# 8x8_328.net
KiCad netlist of a schematic drawn in EAGLE
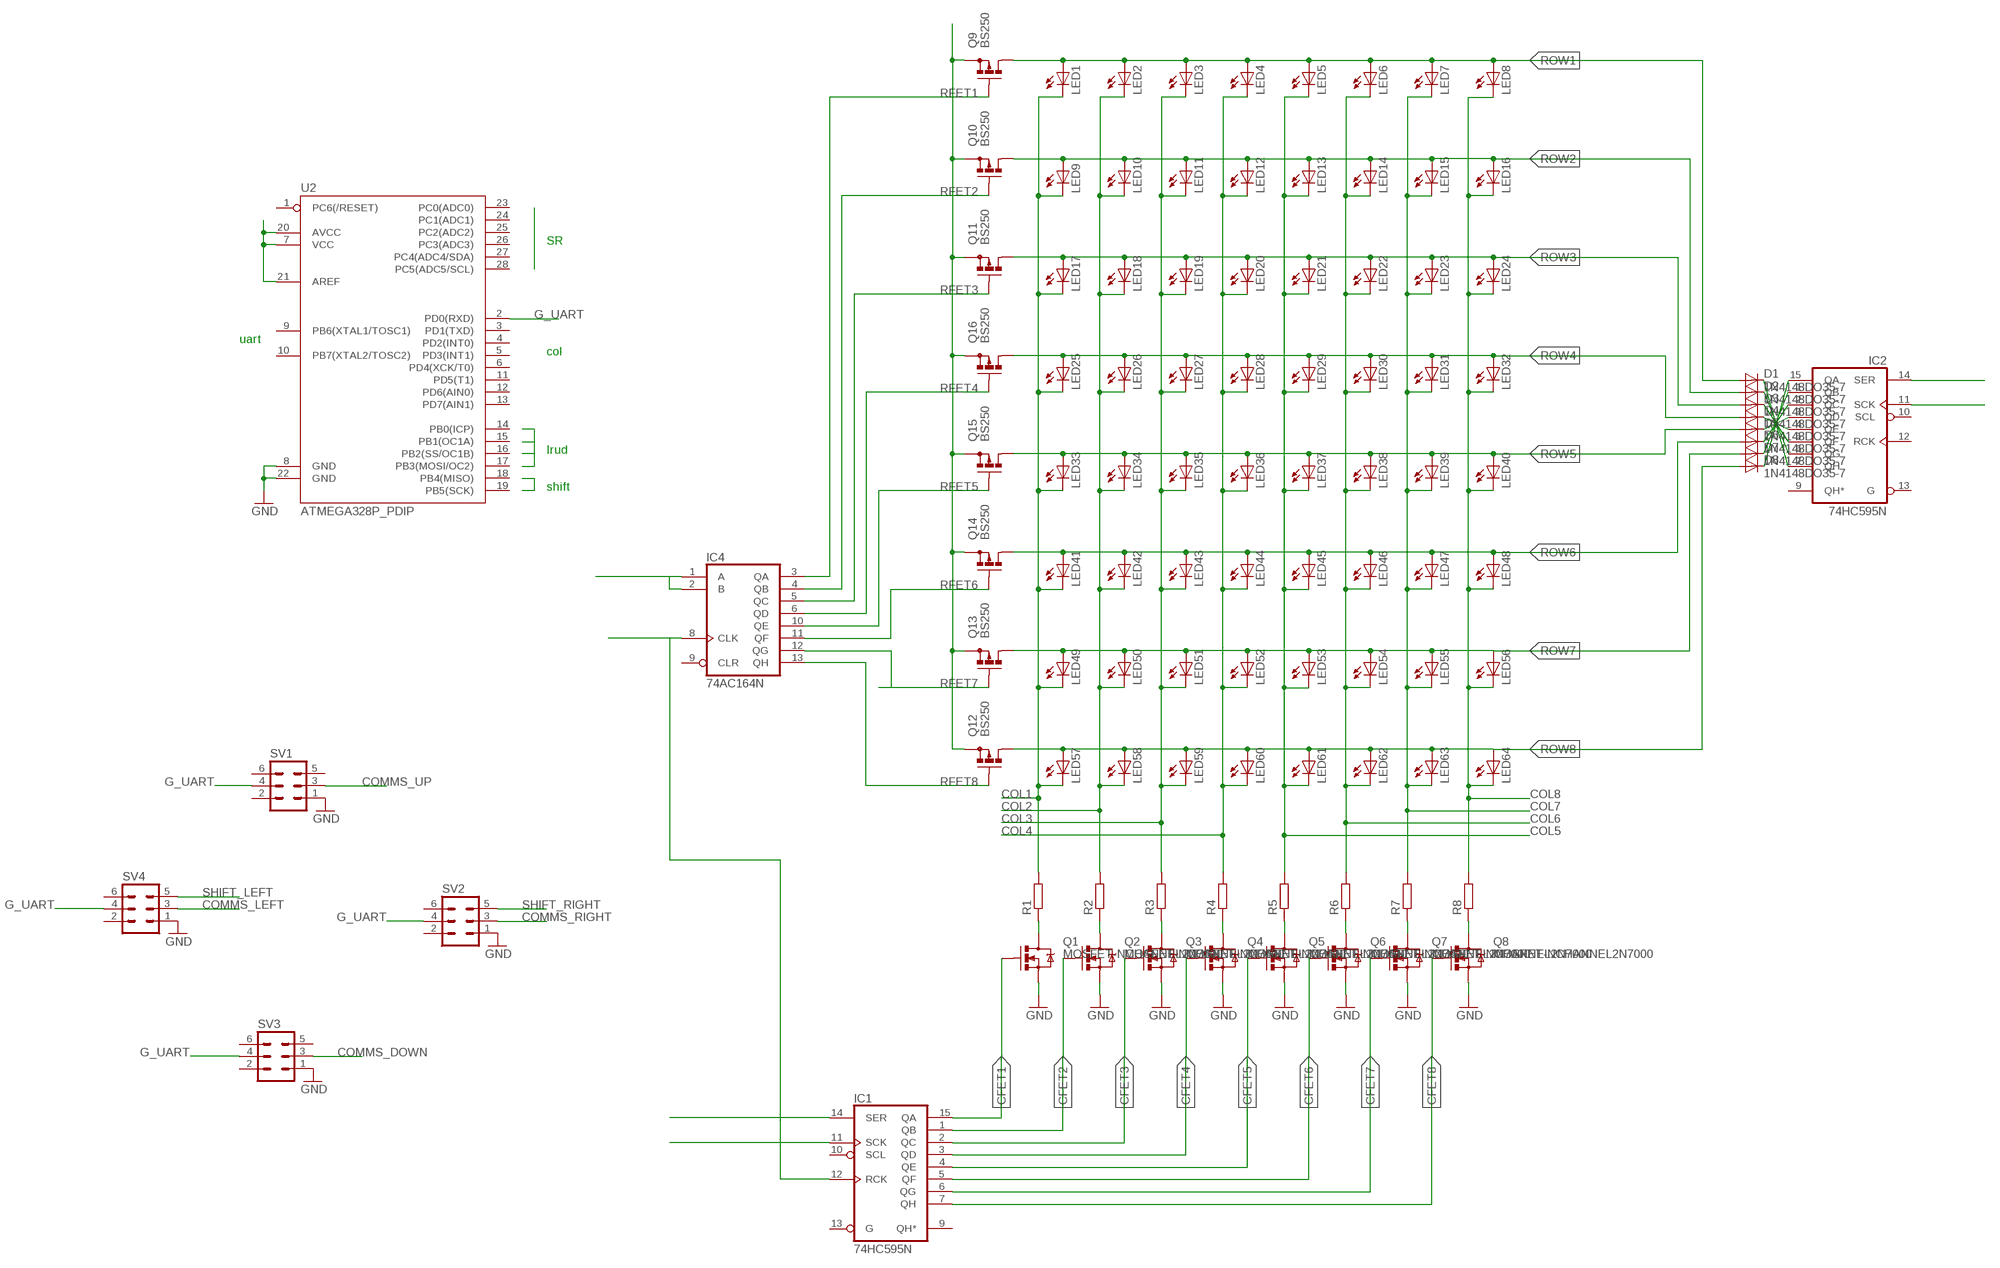
[diagram p0: schematic, sheet 1]

(export (version "E")
  (design (tool "Eeschema 10.0.6"))
  (components
    (comp (ref "D1")
      (value "1N4148DO35-7")
      (footprint "eagle-import:DO35-7")
      (libsource (lib "eagle-import") (part "1N4148DO35-7"))
    )
    (comp (ref "D2")
      (value "1N4148DO35-7")
      (footprint "eagle-import:DO35-7")
      (libsource (lib "eagle-import") (part "1N4148DO35-7"))
    )
    (comp (ref "D3")
      (value "1N4148DO35-7")
      (footprint "eagle-import:DO35-7")
      (libsource (lib "eagle-import") (part "1N4148DO35-7"))
    )
    (comp (ref "D4")
      (value "1N4148DO35-7")
      (footprint "eagle-import:DO35-7")
      (libsource (lib "eagle-import") (part "1N4148DO35-7"))
    )
    (comp (ref "D5")
      (value "1N4148DO35-7")
      (footprint "eagle-import:DO35-7")
      (libsource (lib "eagle-import") (part "1N4148DO35-7"))
    )
    (comp (ref "D6")
      (value "1N4148DO35-7")
      (footprint "eagle-import:DO35-7")
      (libsource (lib "eagle-import") (part "1N4148DO35-7"))
    )
    (comp (ref "D7")
      (value "1N4148DO35-7")
      (footprint "eagle-import:DO35-7")
      (libsource (lib "eagle-import") (part "1N4148DO35-7"))
    )
    (comp (ref "D8")
      (value "1N4148DO35-7")
      (footprint "eagle-import:DO35-7")
      (libsource (lib "eagle-import") (part "1N4148DO35-7"))
    )
    (comp (ref "IC1")
      (value "74HC595N")
      (footprint "eagle-import:DIL16")
      (libsource (lib "eagle-import") (part "74595NHC"))
    )
    (comp (ref "IC2")
      (value "74HC595N")
      (footprint "eagle-import:DIL16")
      (libsource (lib "eagle-import") (part "74595NHC"))
    )
    (comp (ref "IC4")
      (value "74AC164N")
      (footprint "eagle-import:DIL14")
      (libsource (lib "eagle-import") (part "74164NAC"))
    )
    (comp (ref "LED1")
      (value "LED5MM")
      (footprint "eagle-import:LED5MM")
      (libsource (lib "eagle-import") (part "LED5MM"))
    )
    (comp (ref "LED2")
      (value "LED5MM")
      (footprint "eagle-import:LED5MM")
      (libsource (lib "eagle-import") (part "LED5MM"))
    )
    (comp (ref "LED3")
      (value "LED5MM")
      (footprint "eagle-import:LED5MM")
      (libsource (lib "eagle-import") (part "LED5MM"))
    )
    (comp (ref "LED4")
      (value "LED5MM")
      (footprint "eagle-import:LED5MM")
      (libsource (lib "eagle-import") (part "LED5MM"))
    )
    (comp (ref "LED5")
      (value "LED5MM")
      (footprint "eagle-import:LED5MM")
      (libsource (lib "eagle-import") (part "LED5MM"))
    )
    (comp (ref "LED6")
      (value "LED5MM")
      (footprint "eagle-import:LED5MM")
      (libsource (lib "eagle-import") (part "LED5MM"))
    )
    (comp (ref "LED7")
      (value "LED5MM")
      (footprint "eagle-import:LED5MM")
      (libsource (lib "eagle-import") (part "LED5MM"))
    )
    (comp (ref "LED8")
      (value "LED5MM")
      (footprint "eagle-import:LED5MM")
      (libsource (lib "eagle-import") (part "LED5MM"))
    )
    (comp (ref "LED9")
      (value "LED5MM")
      (footprint "eagle-import:LED5MM")
      (libsource (lib "eagle-import") (part "LED5MM"))
    )
    (comp (ref "LED10")
      (value "LED5MM")
      (footprint "eagle-import:LED5MM")
      (libsource (lib "eagle-import") (part "LED5MM"))
    )
    (comp (ref "LED11")
      (value "LED5MM")
      (footprint "eagle-import:LED5MM")
      (libsource (lib "eagle-import") (part "LED5MM"))
    )
    (comp (ref "LED12")
      (value "LED5MM")
      (footprint "eagle-import:LED5MM")
      (libsource (lib "eagle-import") (part "LED5MM"))
    )
    (comp (ref "LED13")
      (value "LED5MM")
      (footprint "eagle-import:LED5MM")
      (libsource (lib "eagle-import") (part "LED5MM"))
    )
    (comp (ref "LED14")
      (value "LED5MM")
      (footprint "eagle-import:LED5MM")
      (libsource (lib "eagle-import") (part "LED5MM"))
    )
    (comp (ref "LED15")
      (value "LED5MM")
      (footprint "eagle-import:LED5MM")
      (libsource (lib "eagle-import") (part "LED5MM"))
    )
    (comp (ref "LED16")
      (value "LED5MM")
      (footprint "eagle-import:LED5MM")
      (libsource (lib "eagle-import") (part "LED5MM"))
    )
    (comp (ref "LED17")
      (value "LED5MM")
      (footprint "eagle-import:LED5MM")
      (libsource (lib "eagle-import") (part "LED5MM"))
    )
    (comp (ref "LED18")
      (value "LED5MM")
      (footprint "eagle-import:LED5MM")
      (libsource (lib "eagle-import") (part "LED5MM"))
    )
    (comp (ref "LED19")
      (value "LED5MM")
      (footprint "eagle-import:LED5MM")
      (libsource (lib "eagle-import") (part "LED5MM"))
    )
    (comp (ref "LED20")
      (value "LED5MM")
      (footprint "eagle-import:LED5MM")
      (libsource (lib "eagle-import") (part "LED5MM"))
    )
    (comp (ref "LED21")
      (value "LED5MM")
      (footprint "eagle-import:LED5MM")
      (libsource (lib "eagle-import") (part "LED5MM"))
    )
    (comp (ref "LED22")
      (value "LED5MM")
      (footprint "eagle-import:LED5MM")
      (libsource (lib "eagle-import") (part "LED5MM"))
    )
    (comp (ref "LED23")
      (value "LED5MM")
      (footprint "eagle-import:LED5MM")
      (libsource (lib "eagle-import") (part "LED5MM"))
    )
    (comp (ref "LED24")
      (value "LED5MM")
      (footprint "eagle-import:LED5MM")
      (libsource (lib "eagle-import") (part "LED5MM"))
    )
    (comp (ref "LED25")
      (value "LED5MM")
      (footprint "eagle-import:LED5MM")
      (libsource (lib "eagle-import") (part "LED5MM"))
    )
    (comp (ref "LED26")
      (value "LED5MM")
      (footprint "eagle-import:LED5MM")
      (libsource (lib "eagle-import") (part "LED5MM"))
    )
    (comp (ref "LED27")
      (value "LED5MM")
      (footprint "eagle-import:LED5MM")
      (libsource (lib "eagle-import") (part "LED5MM"))
    )
    (comp (ref "LED28")
      (value "LED5MM")
      (footprint "eagle-import:LED5MM")
      (libsource (lib "eagle-import") (part "LED5MM"))
    )
    (comp (ref "LED29")
      (value "LED5MM")
      (footprint "eagle-import:LED5MM")
      (libsource (lib "eagle-import") (part "LED5MM"))
    )
    (comp (ref "LED30")
      (value "LED5MM")
      (footprint "eagle-import:LED5MM")
      (libsource (lib "eagle-import") (part "LED5MM"))
    )
    (comp (ref "LED31")
      (value "LED5MM")
      (footprint "eagle-import:LED5MM")
      (libsource (lib "eagle-import") (part "LED5MM"))
    )
    (comp (ref "LED32")
      (value "LED5MM")
      (footprint "eagle-import:LED5MM")
      (libsource (lib "eagle-import") (part "LED5MM"))
    )
    (comp (ref "LED33")
      (value "LED5MM")
      (footprint "eagle-import:LED5MM")
      (libsource (lib "eagle-import") (part "LED5MM"))
    )
    (comp (ref "LED34")
      (value "LED5MM")
      (footprint "eagle-import:LED5MM")
      (libsource (lib "eagle-import") (part "LED5MM"))
    )
    (comp (ref "LED35")
      (value "LED5MM")
      (footprint "eagle-import:LED5MM")
      (libsource (lib "eagle-import") (part "LED5MM"))
    )
    (comp (ref "LED36")
      (value "LED5MM")
      (footprint "eagle-import:LED5MM")
      (libsource (lib "eagle-import") (part "LED5MM"))
    )
    (comp (ref "LED37")
      (value "LED5MM")
      (footprint "eagle-import:LED5MM")
      (libsource (lib "eagle-import") (part "LED5MM"))
    )
    (comp (ref "LED38")
      (value "LED5MM")
      (footprint "eagle-import:LED5MM")
      (libsource (lib "eagle-import") (part "LED5MM"))
    )
    (comp (ref "LED39")
      (value "LED5MM")
      (footprint "eagle-import:LED5MM")
      (libsource (lib "eagle-import") (part "LED5MM"))
    )
    (comp (ref "LED40")
      (value "LED5MM")
      (footprint "eagle-import:LED5MM")
      (libsource (lib "eagle-import") (part "LED5MM"))
    )
    (comp (ref "LED41")
      (value "LED5MM")
      (footprint "eagle-import:LED5MM")
      (libsource (lib "eagle-import") (part "LED5MM"))
    )
    (comp (ref "LED42")
      (value "LED5MM")
      (footprint "eagle-import:LED5MM")
      (libsource (lib "eagle-import") (part "LED5MM"))
    )
    (comp (ref "LED43")
      (value "LED5MM")
      (footprint "eagle-import:LED5MM")
      (libsource (lib "eagle-import") (part "LED5MM"))
    )
    (comp (ref "LED44")
      (value "LED5MM")
      (footprint "eagle-import:LED5MM")
      (libsource (lib "eagle-import") (part "LED5MM"))
    )
    (comp (ref "LED45")
      (value "LED5MM")
      (footprint "eagle-import:LED5MM")
      (libsource (lib "eagle-import") (part "LED5MM"))
    )
    (comp (ref "LED46")
      (value "LED5MM")
      (footprint "eagle-import:LED5MM")
      (libsource (lib "eagle-import") (part "LED5MM"))
    )
    (comp (ref "LED47")
      (value "LED5MM")
      (footprint "eagle-import:LED5MM")
      (libsource (lib "eagle-import") (part "LED5MM"))
    )
    (comp (ref "LED48")
      (value "LED5MM")
      (footprint "eagle-import:LED5MM")
      (libsource (lib "eagle-import") (part "LED5MM"))
    )
    (comp (ref "LED49")
      (value "LED5MM")
      (footprint "eagle-import:LED5MM")
      (libsource (lib "eagle-import") (part "LED5MM"))
    )
    (comp (ref "LED50")
      (value "LED5MM")
      (footprint "eagle-import:LED5MM")
      (libsource (lib "eagle-import") (part "LED5MM"))
    )
    (comp (ref "LED51")
      (value "LED5MM")
      (footprint "eagle-import:LED5MM")
      (libsource (lib "eagle-import") (part "LED5MM"))
    )
    (comp (ref "LED52")
      (value "LED5MM")
      (footprint "eagle-import:LED5MM")
      (libsource (lib "eagle-import") (part "LED5MM"))
    )
    (comp (ref "LED53")
      (value "LED5MM")
      (footprint "eagle-import:LED5MM")
      (libsource (lib "eagle-import") (part "LED5MM"))
    )
    (comp (ref "LED54")
      (value "LED5MM")
      (footprint "eagle-import:LED5MM")
      (libsource (lib "eagle-import") (part "LED5MM"))
    )
    (comp (ref "LED55")
      (value "LED5MM")
      (footprint "eagle-import:LED5MM")
      (libsource (lib "eagle-import") (part "LED5MM"))
    )
    (comp (ref "LED56")
      (value "LED5MM")
      (footprint "eagle-import:LED5MM")
      (libsource (lib "eagle-import") (part "LED5MM"))
    )
    (comp (ref "LED57")
      (value "LED5MM")
      (footprint "eagle-import:LED5MM")
      (libsource (lib "eagle-import") (part "LED5MM"))
    )
    (comp (ref "LED58")
      (value "LED5MM")
      (footprint "eagle-import:LED5MM")
      (libsource (lib "eagle-import") (part "LED5MM"))
    )
    (comp (ref "LED59")
      (value "LED5MM")
      (footprint "eagle-import:LED5MM")
      (libsource (lib "eagle-import") (part "LED5MM"))
    )
    (comp (ref "LED60")
      (value "LED5MM")
      (footprint "eagle-import:LED5MM")
      (libsource (lib "eagle-import") (part "LED5MM"))
    )
    (comp (ref "LED61")
      (value "LED5MM")
      (footprint "eagle-import:LED5MM")
      (libsource (lib "eagle-import") (part "LED5MM"))
    )
    (comp (ref "LED62")
      (value "LED5MM")
      (footprint "eagle-import:LED5MM")
      (libsource (lib "eagle-import") (part "LED5MM"))
    )
    (comp (ref "LED63")
      (value "LED5MM")
      (footprint "eagle-import:LED5MM")
      (libsource (lib "eagle-import") (part "LED5MM"))
    )
    (comp (ref "LED64")
      (value "LED5MM")
      (footprint "eagle-import:LED5MM")
      (libsource (lib "eagle-import") (part "LED5MM"))
    )
    (comp (ref "Q1")
      (value "MOSFET-NCHANNEL2N7000")
      (footprint "eagle-import:TO-92")
      (libsource (lib "eagle-import") (part "MOSFET-NCHANNEL2N7000"))
    )
    (comp (ref "Q2")
      (value "MOSFET-NCHANNEL2N7000")
      (footprint "eagle-import:TO-92")
      (libsource (lib "eagle-import") (part "MOSFET-NCHANNEL2N7000"))
    )
    (comp (ref "Q3")
      (value "MOSFET-NCHANNEL2N7000")
      (footprint "eagle-import:TO-92")
      (libsource (lib "eagle-import") (part "MOSFET-NCHANNEL2N7000"))
    )
    (comp (ref "Q4")
      (value "MOSFET-NCHANNEL2N7000")
      (footprint "eagle-import:TO-92")
      (libsource (lib "eagle-import") (part "MOSFET-NCHANNEL2N7000"))
    )
    (comp (ref "Q5")
      (value "MOSFET-NCHANNEL2N7000")
      (footprint "eagle-import:TO-92")
      (libsource (lib "eagle-import") (part "MOSFET-NCHANNEL2N7000"))
    )
    (comp (ref "Q6")
      (value "MOSFET-NCHANNEL2N7000")
      (footprint "eagle-import:TO-92")
      (libsource (lib "eagle-import") (part "MOSFET-NCHANNEL2N7000"))
    )
    (comp (ref "Q7")
      (value "MOSFET-NCHANNEL2N7000")
      (footprint "eagle-import:TO-92")
      (libsource (lib "eagle-import") (part "MOSFET-NCHANNEL2N7000"))
    )
    (comp (ref "Q8")
      (value "MOSFET-NCHANNEL2N7000")
      (footprint "eagle-import:TO-92")
      (libsource (lib "eagle-import") (part "MOSFET-NCHANNEL2N7000"))
    )
    (comp (ref "Q9")
      (value "BS250")
      (footprint "eagle-import:SOT54E")
      (libsource (lib "eagle-import") (part "BS250"))
    )
    (comp (ref "Q10")
      (value "BS250")
      (footprint "eagle-import:SOT54E")
      (libsource (lib "eagle-import") (part "BS250"))
    )
    (comp (ref "Q11")
      (value "BS250")
      (footprint "eagle-import:SOT54E")
      (libsource (lib "eagle-import") (part "BS250"))
    )
    (comp (ref "Q12")
      (value "BS250")
      (footprint "eagle-import:SOT54E")
      (libsource (lib "eagle-import") (part "BS250"))
    )
    (comp (ref "Q13")
      (value "BS250")
      (footprint "eagle-import:SOT54E")
      (libsource (lib "eagle-import") (part "BS250"))
    )
    (comp (ref "Q14")
      (value "BS250")
      (footprint "eagle-import:SOT54E")
      (libsource (lib "eagle-import") (part "BS250"))
    )
    (comp (ref "Q15")
      (value "BS250")
      (footprint "eagle-import:SOT54E")
      (libsource (lib "eagle-import") (part "BS250"))
    )
    (comp (ref "Q16")
      (value "BS250")
      (footprint "eagle-import:SOT54E")
      (libsource (lib "eagle-import") (part "BS250"))
    )
    (comp (ref "R1")
      (value "R-EU_0207/10")
      (footprint "eagle-import:0207_10")
      (libsource (lib "eagle-import") (part "R-EU_0207/10"))
    )
    (comp (ref "R2")
      (value "R-EU_0207/10")
      (footprint "eagle-import:0207_10")
      (libsource (lib "eagle-import") (part "R-EU_0207/10"))
    )
    (comp (ref "R3")
      (value "R-EU_0207/10")
      (footprint "eagle-import:0207_10")
      (libsource (lib "eagle-import") (part "R-EU_0207/10"))
    )
    (comp (ref "R4")
      (value "R-EU_0207/10")
      (footprint "eagle-import:0207_10")
      (libsource (lib "eagle-import") (part "R-EU_0207/10"))
    )
    (comp (ref "R5")
      (value "R-EU_0207/10")
      (footprint "eagle-import:0207_10")
      (libsource (lib "eagle-import") (part "R-EU_0207/10"))
    )
    (comp (ref "R6")
      (value "R-EU_0207/10")
      (footprint "eagle-import:0207_10")
      (libsource (lib "eagle-import") (part "R-EU_0207/10"))
    )
    (comp (ref "R7")
      (value "R-EU_0207/10")
      (footprint "eagle-import:0207_10")
      (libsource (lib "eagle-import") (part "R-EU_0207/10"))
    )
    (comp (ref "R8")
      (value "R-EU_0207/10")
      (footprint "eagle-import:0207_10")
      (libsource (lib "eagle-import") (part "R-EU_0207/10"))
    )
    (comp (ref "SV1")
      (value "MA03-2")
      (footprint "eagle-import:MA03-2")
      (libsource (lib "eagle-import") (part "MA03-2"))
    )
    (comp (ref "SV2")
      (value "MA03-2")
      (footprint "eagle-import:MA03-2")
      (libsource (lib "eagle-import") (part "MA03-2"))
    )
    (comp (ref "SV3")
      (value "MA03-2")
      (footprint "eagle-import:MA03-2")
      (libsource (lib "eagle-import") (part "MA03-2"))
    )
    (comp (ref "SV4")
      (value "MA03-2")
      (footprint "eagle-import:MA03-2")
      (libsource (lib "eagle-import") (part "MA03-2"))
    )
    (comp (ref "U2")
      (value "ATMEGA328P_PDIP")
      (footprint "eagle-import:DIL28-3")
      (libsource (lib "eagle-import") (part "ATMEGA328P_PDIP"))
    )
  )
  (nets
    (net (code "1") (name "/COL1") (class "Default")
      (node (ref "LED1") (pin "K") (pinfunction "C_K") (pintype "passive"))
      (node (ref "LED17") (pin "K") (pinfunction "C_K") (pintype "passive"))
      (node (ref "LED25") (pin "K") (pinfunction "C_K") (pintype "passive"))
      (node (ref "LED33") (pin "K") (pinfunction "C_K") (pintype "passive"))
      (node (ref "LED41") (pin "K") (pinfunction "C_K") (pintype "passive"))
      (node (ref "LED49") (pin "K") (pinfunction "C_K") (pintype "passive"))
      (node (ref "LED57") (pin "K") (pinfunction "C_K") (pintype "passive"))
      (node (ref "LED9") (pin "K") (pinfunction "C_K") (pintype "passive"))
      (node (ref "R1") (pin "2") (pinfunction "2_2") (pintype "passive"))
    )
    (net (code "2") (name "/COL2") (class "Default")
      (node (ref "LED10") (pin "K") (pinfunction "C_K") (pintype "passive"))
      (node (ref "LED18") (pin "K") (pinfunction "C_K") (pintype "passive"))
      (node (ref "LED2") (pin "K") (pinfunction "C_K") (pintype "passive"))
      (node (ref "LED26") (pin "K") (pinfunction "C_K") (pintype "passive"))
      (node (ref "LED34") (pin "K") (pinfunction "C_K") (pintype "passive"))
      (node (ref "LED42") (pin "K") (pinfunction "C_K") (pintype "passive"))
      (node (ref "LED50") (pin "K") (pinfunction "C_K") (pintype "passive"))
      (node (ref "LED58") (pin "K") (pinfunction "C_K") (pintype "passive"))
      (node (ref "R2") (pin "2") (pinfunction "2_2") (pintype "passive"))
    )
    (net (code "3") (name "/COL3") (class "Default")
      (node (ref "LED11") (pin "K") (pinfunction "C_K") (pintype "passive"))
      (node (ref "LED19") (pin "K") (pinfunction "C_K") (pintype "passive"))
      (node (ref "LED27") (pin "K") (pinfunction "C_K") (pintype "passive"))
      (node (ref "LED3") (pin "K") (pinfunction "C_K") (pintype "passive"))
      (node (ref "LED35") (pin "K") (pinfunction "C_K") (pintype "passive"))
      (node (ref "LED43") (pin "K") (pinfunction "C_K") (pintype "passive"))
      (node (ref "LED51") (pin "K") (pinfunction "C_K") (pintype "passive"))
      (node (ref "LED59") (pin "K") (pinfunction "C_K") (pintype "passive"))
      (node (ref "R3") (pin "2") (pinfunction "2_2") (pintype "passive"))
    )
    (net (code "4") (name "/COL4") (class "Default")
      (node (ref "LED12") (pin "K") (pinfunction "C_K") (pintype "passive"))
      (node (ref "LED20") (pin "K") (pinfunction "C_K") (pintype "passive"))
      (node (ref "LED28") (pin "K") (pinfunction "C_K") (pintype "passive"))
      (node (ref "LED36") (pin "K") (pinfunction "C_K") (pintype "passive"))
      (node (ref "LED4") (pin "K") (pinfunction "C_K") (pintype "passive"))
      (node (ref "LED44") (pin "K") (pinfunction "C_K") (pintype "passive"))
      (node (ref "LED52") (pin "K") (pinfunction "C_K") (pintype "passive"))
      (node (ref "LED60") (pin "K") (pinfunction "C_K") (pintype "passive"))
      (node (ref "R4") (pin "2") (pinfunction "2_2") (pintype "passive"))
    )
    (net (code "5") (name "/COL5") (class "Default")
      (node (ref "LED13") (pin "K") (pinfunction "C_K") (pintype "passive"))
      (node (ref "LED21") (pin "K") (pinfunction "C_K") (pintype "passive"))
      (node (ref "LED29") (pin "K") (pinfunction "C_K") (pintype "passive"))
      (node (ref "LED37") (pin "K") (pinfunction "C_K") (pintype "passive"))
      (node (ref "LED45") (pin "K") (pinfunction "C_K") (pintype "passive"))
      (node (ref "LED5") (pin "K") (pinfunction "C_K") (pintype "passive"))
      (node (ref "LED53") (pin "K") (pinfunction "C_K") (pintype "passive"))
      (node (ref "LED61") (pin "K") (pinfunction "C_K") (pintype "passive"))
      (node (ref "R5") (pin "2") (pinfunction "2_2") (pintype "passive"))
    )
    (net (code "6") (name "/COL6") (class "Default")
      (node (ref "LED14") (pin "K") (pinfunction "C_K") (pintype "passive"))
      (node (ref "LED22") (pin "K") (pinfunction "C_K") (pintype "passive"))
      (node (ref "LED30") (pin "K") (pinfunction "C_K") (pintype "passive"))
      (node (ref "LED38") (pin "K") (pinfunction "C_K") (pintype "passive"))
      (node (ref "LED46") (pin "K") (pinfunction "C_K") (pintype "passive"))
      (node (ref "LED54") (pin "K") (pinfunction "C_K") (pintype "passive"))
      (node (ref "LED6") (pin "K") (pinfunction "C_K") (pintype "passive"))
      (node (ref "LED62") (pin "K") (pinfunction "C_K") (pintype "passive"))
      (node (ref "R6") (pin "2") (pinfunction "2_2") (pintype "passive"))
    )
    (net (code "7") (name "/COL7") (class "Default")
      (node (ref "LED15") (pin "K") (pinfunction "C_K") (pintype "passive"))
      (node (ref "LED23") (pin "K") (pinfunction "C_K") (pintype "passive"))
      (node (ref "LED31") (pin "K") (pinfunction "C_K") (pintype "passive"))
      (node (ref "LED39") (pin "K") (pinfunction "C_K") (pintype "passive"))
      (node (ref "LED47") (pin "K") (pinfunction "C_K") (pintype "passive"))
      (node (ref "LED55") (pin "K") (pinfunction "C_K") (pintype "passive"))
      (node (ref "LED63") (pin "K") (pinfunction "C_K") (pintype "passive"))
      (node (ref "LED7") (pin "K") (pinfunction "C_K") (pintype "passive"))
      (node (ref "R7") (pin "2") (pinfunction "2_2") (pintype "passive"))
    )
    (net (code "8") (name "/COL8") (class "Default")
      (node (ref "LED16") (pin "K") (pinfunction "C_K") (pintype "passive"))
      (node (ref "LED24") (pin "K") (pinfunction "C_K") (pintype "passive"))
      (node (ref "LED32") (pin "K") (pinfunction "C_K") (pintype "passive"))
      (node (ref "LED40") (pin "K") (pinfunction "C_K") (pintype "passive"))
      (node (ref "LED48") (pin "K") (pinfunction "C_K") (pintype "passive"))
      (node (ref "LED56") (pin "K") (pinfunction "C_K") (pintype "passive"))
      (node (ref "LED64") (pin "K") (pinfunction "C_K") (pintype "passive"))
      (node (ref "LED8") (pin "K") (pinfunction "C_K") (pintype "passive"))
      (node (ref "R8") (pin "2") (pinfunction "2_2") (pintype "passive"))
    )
    (net (code "9") (name "/COMMS_DOWN") (class "Default")
      (node (ref "SV3") (pin "3") (pinfunction "3_3") (pintype "passive"))
    )
    (net (code "10") (name "/COMMS_LEFT") (class "Default")
      (node (ref "SV4") (pin "3") (pinfunction "3_3") (pintype "passive"))
    )
    (net (code "11") (name "/COMMS_RIGHT") (class "Default")
      (node (ref "SV2") (pin "3") (pinfunction "3_3") (pintype "passive"))
    )
    (net (code "12") (name "/COMMS_UP") (class "Default")
      (node (ref "SV1") (pin "3") (pinfunction "3_3") (pintype "passive"))
    )
    (net (code "13") (name "/G_UART") (class "Default")
      (node (ref "SV1") (pin "4") (pinfunction "4_4") (pintype "passive"))
      (node (ref "SV2") (pin "4") (pinfunction "4_4") (pintype "passive"))
      (node (ref "SV3") (pin "4") (pinfunction "4_4") (pintype "passive"))
      (node (ref "SV4") (pin "4") (pinfunction "4_4") (pintype "passive"))
      (node (ref "U2") (pin "2") (pinfunction "PD0(RXD)_2") (pintype "bidirectional"))
    )
    (net (code "14") (name "/RFET1") (class "Default")
      (node (ref "IC4") (pin "3") (pinfunction "QA_3") (pintype "output"))
      (node (ref "Q9") (pin "G") (pinfunction "G_G") (pintype "passive"))
    )
    (net (code "15") (name "/RFET2") (class "Default")
      (node (ref "IC4") (pin "4") (pinfunction "QB_4") (pintype "output"))
      (node (ref "Q10") (pin "G") (pinfunction "G_G") (pintype "passive"))
    )
    (net (code "16") (name "/RFET3") (class "Default")
      (node (ref "IC4") (pin "5") (pinfunction "QC_5") (pintype "output"))
      (node (ref "Q11") (pin "G") (pinfunction "G_G") (pintype "passive"))
    )
    (net (code "17") (name "/RFET4") (class "Default")
      (node (ref "IC4") (pin "6") (pinfunction "QD_6") (pintype "output"))
      (node (ref "Q16") (pin "G") (pinfunction "G_G") (pintype "passive"))
    )
    (net (code "18") (name "/RFET5") (class "Default")
      (node (ref "IC4") (pin "10") (pinfunction "QE_10") (pintype "output"))
      (node (ref "Q15") (pin "G") (pinfunction "G_G") (pintype "passive"))
    )
    (net (code "19") (name "/RFET6") (class "Default")
      (node (ref "IC4") (pin "11") (pinfunction "QF_11") (pintype "output"))
      (node (ref "Q14") (pin "G") (pinfunction "G_G") (pintype "passive"))
    )
    (net (code "20") (name "/RFET7") (class "Default")
      (node (ref "IC4") (pin "12") (pinfunction "QG_12") (pintype "output"))
      (node (ref "Q13") (pin "G") (pinfunction "G_G") (pintype "passive"))
    )
    (net (code "21") (name "/RFET8") (class "Default")
      (node (ref "IC4") (pin "13") (pinfunction "QH_13") (pintype "output"))
      (node (ref "Q12") (pin "G") (pinfunction "G_G") (pintype "passive"))
    )
    (net (code "22") (name "/SHIFT_LEFT") (class "Default")
      (node (ref "SV4") (pin "5") (pinfunction "5_5") (pintype "passive"))
    )
    (net (code "23") (name "/SHIFT_RIGHT") (class "Default")
      (node (ref "SV2") (pin "5") (pinfunction "5_5") (pintype "passive"))
    )
    (net (code "24") (name "CFET1") (class "Default")
      (node (ref "IC1") (pin "15") (pinfunction "QA_15") (pintype "tri_state"))
      (node (ref "Q1") (pin "2") (pinfunction "G_2") (pintype "passive"))
    )
    (net (code "25") (name "CFET2") (class "Default")
      (node (ref "IC1") (pin "1") (pinfunction "QB_1") (pintype "tri_state"))
      (node (ref "Q2") (pin "2") (pinfunction "G_2") (pintype "passive"))
    )
    (net (code "26") (name "CFET3") (class "Default")
      (node (ref "IC1") (pin "2") (pinfunction "QC_2") (pintype "tri_state"))
      (node (ref "Q3") (pin "2") (pinfunction "G_2") (pintype "passive"))
    )
    (net (code "27") (name "CFET4") (class "Default")
      (node (ref "IC1") (pin "3") (pinfunction "QD_3") (pintype "tri_state"))
      (node (ref "Q4") (pin "2") (pinfunction "G_2") (pintype "passive"))
    )
    (net (code "28") (name "CFET5") (class "Default")
      (node (ref "IC1") (pin "4") (pinfunction "QE_4") (pintype "tri_state"))
      (node (ref "Q5") (pin "2") (pinfunction "G_2") (pintype "passive"))
    )
    (net (code "29") (name "CFET6") (class "Default")
      (node (ref "IC1") (pin "5") (pinfunction "QF_5") (pintype "tri_state"))
      (node (ref "Q6") (pin "2") (pinfunction "G_2") (pintype "passive"))
    )
    (net (code "30") (name "CFET7") (class "Default")
      (node (ref "IC1") (pin "6") (pinfunction "QG_6") (pintype "tri_state"))
      (node (ref "Q7") (pin "2") (pinfunction "G_2") (pintype "passive"))
    )
    (net (code "31") (name "CFET8") (class "Default")
      (node (ref "IC1") (pin "7") (pinfunction "QH_7") (pintype "tri_state"))
      (node (ref "Q8") (pin "2") (pinfunction "G_2") (pintype "passive"))
    )
    (net (code "32") (name "GND") (class "Default")
      (node (ref "Q1") (pin "1") (pinfunction "S_1") (pintype "passive"))
      (node (ref "Q2") (pin "1") (pinfunction "S_1") (pintype "passive"))
      (node (ref "Q3") (pin "1") (pinfunction "S_1") (pintype "passive"))
      (node (ref "Q4") (pin "1") (pinfunction "S_1") (pintype "passive"))
      (node (ref "Q5") (pin "1") (pinfunction "S_1") (pintype "passive"))
      (node (ref "Q6") (pin "1") (pinfunction "S_1") (pintype "passive"))
      (node (ref "Q7") (pin "1") (pinfunction "S_1") (pintype "passive"))
      (node (ref "Q8") (pin "1") (pinfunction "S_1") (pintype "passive"))
      (node (ref "SV1") (pin "1") (pinfunction "1_1") (pintype "passive"))
      (node (ref "SV2") (pin "1") (pinfunction "1_1") (pintype "passive"))
      (node (ref "SV3") (pin "1") (pinfunction "1_1") (pintype "passive"))
      (node (ref "SV4") (pin "1") (pinfunction "1_1") (pintype "passive"))
      (node (ref "U2") (pin "22") (pinfunction "GND_22") (pintype "bidirectional"))
      (node (ref "U2") (pin "8") (pinfunction "GND_8") (pintype "bidirectional"))
    )
    (net (code "33") (name "Net-(IC1A-RCK)") (class "Default")
      (node (ref "IC1") (pin "12") (pinfunction "RCK_12") (pintype "input"))
      (node (ref "IC4") (pin "8") (pinfunction "CLK_8") (pintype "input"))
    )
    (net (code "34") (name "Net-(IC2A-QA)") (class "Default")
      (node (ref "D8") (pin "C") (pinfunction "C_C") (pintype "passive"))
      (node (ref "IC2") (pin "15") (pinfunction "QA_15") (pintype "tri_state"))
    )
    (net (code "35") (name "Net-(IC2A-QB)") (class "Default")
      (node (ref "D7") (pin "C") (pinfunction "C_C") (pintype "passive"))
      (node (ref "IC2") (pin "1") (pinfunction "QB_1") (pintype "tri_state"))
    )
    (net (code "36") (name "Net-(IC2A-QC)") (class "Default")
      (node (ref "D6") (pin "C") (pinfunction "C_C") (pintype "passive"))
      (node (ref "IC2") (pin "2") (pinfunction "QC_2") (pintype "tri_state"))
    )
    (net (code "37") (name "Net-(IC2A-QD)") (class "Default")
      (node (ref "D5") (pin "C") (pinfunction "C_C") (pintype "passive"))
      (node (ref "IC2") (pin "3") (pinfunction "QD_3") (pintype "tri_state"))
    )
    (net (code "38") (name "Net-(IC2A-QE)") (class "Default")
      (node (ref "D4") (pin "C") (pinfunction "C_C") (pintype "passive"))
      (node (ref "IC2") (pin "4") (pinfunction "QE_4") (pintype "tri_state"))
    )
    (net (code "39") (name "Net-(IC2A-QF)") (class "Default")
      (node (ref "D3") (pin "C") (pinfunction "C_C") (pintype "passive"))
      (node (ref "IC2") (pin "5") (pinfunction "QF_5") (pintype "tri_state"))
    )
    (net (code "40") (name "Net-(IC2A-QG)") (class "Default")
      (node (ref "D2") (pin "C") (pinfunction "C_C") (pintype "passive"))
      (node (ref "IC2") (pin "6") (pinfunction "QG_6") (pintype "tri_state"))
    )
    (net (code "41") (name "Net-(IC2A-QH)") (class "Default")
      (node (ref "D1") (pin "C") (pinfunction "C_C") (pintype "passive"))
      (node (ref "IC2") (pin "7") (pinfunction "QH_7") (pintype "tri_state"))
    )
    (net (code "42") (name "Net-(IC4A-A)") (class "Default")
      (node (ref "IC4") (pin "1") (pinfunction "A_1") (pintype "input"))
      (node (ref "IC4") (pin "2") (pinfunction "B_2") (pintype "input"))
    )
    (net (code "43") (name "Net-(Q1-D)") (class "Default")
      (node (ref "Q1") (pin "3") (pinfunction "D_3") (pintype "passive"))
      (node (ref "R1") (pin "1") (pinfunction "1_1") (pintype "passive"))
    )
    (net (code "44") (name "Net-(Q2-D)") (class "Default")
      (node (ref "Q2") (pin "3") (pinfunction "D_3") (pintype "passive"))
      (node (ref "R2") (pin "1") (pinfunction "1_1") (pintype "passive"))
    )
    (net (code "45") (name "Net-(Q3-D)") (class "Default")
      (node (ref "Q3") (pin "3") (pinfunction "D_3") (pintype "passive"))
      (node (ref "R3") (pin "1") (pinfunction "1_1") (pintype "passive"))
    )
    (net (code "46") (name "Net-(Q4-D)") (class "Default")
      (node (ref "Q4") (pin "3") (pinfunction "D_3") (pintype "passive"))
      (node (ref "R4") (pin "1") (pinfunction "1_1") (pintype "passive"))
    )
    (net (code "47") (name "Net-(Q5-D)") (class "Default")
      (node (ref "Q5") (pin "3") (pinfunction "D_3") (pintype "passive"))
      (node (ref "R5") (pin "1") (pinfunction "1_1") (pintype "passive"))
    )
    (net (code "48") (name "Net-(Q6-D)") (class "Default")
      (node (ref "Q6") (pin "3") (pinfunction "D_3") (pintype "passive"))
      (node (ref "R6") (pin "1") (pinfunction "1_1") (pintype "passive"))
    )
    (net (code "49") (name "Net-(Q7-D)") (class "Default")
      (node (ref "Q7") (pin "3") (pinfunction "D_3") (pintype "passive"))
      (node (ref "R7") (pin "1") (pinfunction "1_1") (pintype "passive"))
    )
    (net (code "50") (name "Net-(Q8-D)") (class "Default")
      (node (ref "Q8") (pin "3") (pinfunction "D_3") (pintype "passive"))
      (node (ref "R8") (pin "1") (pinfunction "1_1") (pintype "passive"))
    )
    (net (code "51") (name "Net-(Q10-PadS)") (class "Default")
      (node (ref "Q10") (pin "S") (pinfunction "S_S") (pintype "passive"))
      (node (ref "Q11") (pin "S") (pinfunction "S_S") (pintype "passive"))
      (node (ref "Q12") (pin "S") (pinfunction "S_S") (pintype "passive"))
      (node (ref "Q13") (pin "S") (pinfunction "S_S") (pintype "passive"))
      (node (ref "Q14") (pin "S") (pinfunction "S_S") (pintype "passive"))
      (node (ref "Q15") (pin "S") (pinfunction "S_S") (pintype "passive"))
      (node (ref "Q16") (pin "S") (pinfunction "S_S") (pintype "passive"))
      (node (ref "Q9") (pin "S") (pinfunction "S_S") (pintype "passive"))
    )
    (net (code "52") (name "Net-(U2-AREF)") (class "Default")
      (node (ref "U2") (pin "20") (pinfunction "AVCC_20") (pintype "bidirectional"))
      (node (ref "U2") (pin "21") (pinfunction "AREF_21") (pintype "bidirectional"))
      (node (ref "U2") (pin "7") (pinfunction "VCC_7") (pintype "bidirectional"))
    )
    (net (code "53") (name "ROW1") (class "Default")
      (node (ref "D1") (pin "A") (pinfunction "A_A") (pintype "passive"))
      (node (ref "LED1") (pin "A") (pinfunction "A_A") (pintype "passive"))
      (node (ref "LED2") (pin "A") (pinfunction "A_A") (pintype "passive"))
      (node (ref "LED3") (pin "A") (pinfunction "A_A") (pintype "passive"))
      (node (ref "LED4") (pin "A") (pinfunction "A_A") (pintype "passive"))
      (node (ref "LED5") (pin "A") (pinfunction "A_A") (pintype "passive"))
      (node (ref "LED6") (pin "A") (pinfunction "A_A") (pintype "passive"))
      (node (ref "LED7") (pin "A") (pinfunction "A_A") (pintype "passive"))
      (node (ref "LED8") (pin "A") (pinfunction "A_A") (pintype "passive"))
      (node (ref "Q9") (pin "D") (pinfunction "D_D") (pintype "passive"))
    )
    (net (code "54") (name "ROW2") (class "Default")
      (node (ref "D2") (pin "A") (pinfunction "A_A") (pintype "passive"))
      (node (ref "LED10") (pin "A") (pinfunction "A_A") (pintype "passive"))
      (node (ref "LED11") (pin "A") (pinfunction "A_A") (pintype "passive"))
      (node (ref "LED12") (pin "A") (pinfunction "A_A") (pintype "passive"))
      (node (ref "LED13") (pin "A") (pinfunction "A_A") (pintype "passive"))
      (node (ref "LED14") (pin "A") (pinfunction "A_A") (pintype "passive"))
      (node (ref "LED15") (pin "A") (pinfunction "A_A") (pintype "passive"))
      (node (ref "LED16") (pin "A") (pinfunction "A_A") (pintype "passive"))
      (node (ref "LED9") (pin "A") (pinfunction "A_A") (pintype "passive"))
      (node (ref "Q10") (pin "D") (pinfunction "D_D") (pintype "passive"))
    )
    (net (code "55") (name "ROW3") (class "Default")
      (node (ref "D3") (pin "A") (pinfunction "A_A") (pintype "passive"))
      (node (ref "LED17") (pin "A") (pinfunction "A_A") (pintype "passive"))
      (node (ref "LED18") (pin "A") (pinfunction "A_A") (pintype "passive"))
      (node (ref "LED19") (pin "A") (pinfunction "A_A") (pintype "passive"))
      (node (ref "LED20") (pin "A") (pinfunction "A_A") (pintype "passive"))
      (node (ref "LED21") (pin "A") (pinfunction "A_A") (pintype "passive"))
      (node (ref "LED22") (pin "A") (pinfunction "A_A") (pintype "passive"))
      (node (ref "LED23") (pin "A") (pinfunction "A_A") (pintype "passive"))
      (node (ref "LED24") (pin "A") (pinfunction "A_A") (pintype "passive"))
      (node (ref "Q11") (pin "D") (pinfunction "D_D") (pintype "passive"))
    )
    (net (code "56") (name "ROW4") (class "Default")
      (node (ref "D4") (pin "A") (pinfunction "A_A") (pintype "passive"))
      (node (ref "LED25") (pin "A") (pinfunction "A_A") (pintype "passive"))
      (node (ref "LED26") (pin "A") (pinfunction "A_A") (pintype "passive"))
      (node (ref "LED27") (pin "A") (pinfunction "A_A") (pintype "passive"))
      (node (ref "LED28") (pin "A") (pinfunction "A_A") (pintype "passive"))
      (node (ref "LED29") (pin "A") (pinfunction "A_A") (pintype "passive"))
      (node (ref "LED30") (pin "A") (pinfunction "A_A") (pintype "passive"))
      (node (ref "LED31") (pin "A") (pinfunction "A_A") (pintype "passive"))
      (node (ref "LED32") (pin "A") (pinfunction "A_A") (pintype "passive"))
      (node (ref "Q16") (pin "D") (pinfunction "D_D") (pintype "passive"))
    )
    (net (code "57") (name "ROW5") (class "Default")
      (node (ref "D5") (pin "A") (pinfunction "A_A") (pintype "passive"))
      (node (ref "LED33") (pin "A") (pinfunction "A_A") (pintype "passive"))
      (node (ref "LED34") (pin "A") (pinfunction "A_A") (pintype "passive"))
      (node (ref "LED35") (pin "A") (pinfunction "A_A") (pintype "passive"))
      (node (ref "LED36") (pin "A") (pinfunction "A_A") (pintype "passive"))
      (node (ref "LED37") (pin "A") (pinfunction "A_A") (pintype "passive"))
      (node (ref "LED38") (pin "A") (pinfunction "A_A") (pintype "passive"))
      (node (ref "LED39") (pin "A") (pinfunction "A_A") (pintype "passive"))
      (node (ref "LED40") (pin "A") (pinfunction "A_A") (pintype "passive"))
      (node (ref "Q15") (pin "D") (pinfunction "D_D") (pintype "passive"))
    )
    (net (code "58") (name "ROW6") (class "Default")
      (node (ref "D6") (pin "A") (pinfunction "A_A") (pintype "passive"))
      (node (ref "LED41") (pin "A") (pinfunction "A_A") (pintype "passive"))
      (node (ref "LED42") (pin "A") (pinfunction "A_A") (pintype "passive"))
      (node (ref "LED43") (pin "A") (pinfunction "A_A") (pintype "passive"))
      (node (ref "LED44") (pin "A") (pinfunction "A_A") (pintype "passive"))
      (node (ref "LED45") (pin "A") (pinfunction "A_A") (pintype "passive"))
      (node (ref "LED46") (pin "A") (pinfunction "A_A") (pintype "passive"))
      (node (ref "LED47") (pin "A") (pinfunction "A_A") (pintype "passive"))
      (node (ref "LED48") (pin "A") (pinfunction "A_A") (pintype "passive"))
      (node (ref "Q14") (pin "D") (pinfunction "D_D") (pintype "passive"))
    )
    (net (code "59") (name "ROW7") (class "Default")
      (node (ref "D7") (pin "A") (pinfunction "A_A") (pintype "passive"))
      (node (ref "LED49") (pin "A") (pinfunction "A_A") (pintype "passive"))
      (node (ref "LED50") (pin "A") (pinfunction "A_A") (pintype "passive"))
      (node (ref "LED51") (pin "A") (pinfunction "A_A") (pintype "passive"))
      (node (ref "LED52") (pin "A") (pinfunction "A_A") (pintype "passive"))
      (node (ref "LED53") (pin "A") (pinfunction "A_A") (pintype "passive"))
      (node (ref "LED54") (pin "A") (pinfunction "A_A") (pintype "passive"))
      (node (ref "LED55") (pin "A") (pinfunction "A_A") (pintype "passive"))
      (node (ref "LED56") (pin "A") (pinfunction "A_A") (pintype "passive"))
      (node (ref "Q13") (pin "D") (pinfunction "D_D") (pintype "passive"))
    )
    (net (code "60") (name "ROW8") (class "Default")
      (node (ref "D8") (pin "A") (pinfunction "A_A") (pintype "passive"))
      (node (ref "LED57") (pin "A") (pinfunction "A_A") (pintype "passive"))
      (node (ref "LED58") (pin "A") (pinfunction "A_A") (pintype "passive"))
      (node (ref "LED59") (pin "A") (pinfunction "A_A") (pintype "passive"))
      (node (ref "LED60") (pin "A") (pinfunction "A_A") (pintype "passive"))
      (node (ref "LED61") (pin "A") (pinfunction "A_A") (pintype "passive"))
      (node (ref "LED62") (pin "A") (pinfunction "A_A") (pintype "passive"))
      (node (ref "LED63") (pin "A") (pinfunction "A_A") (pintype "passive"))
      (node (ref "LED64") (pin "A") (pinfunction "A_A") (pintype "passive"))
      (node (ref "Q12") (pin "D") (pinfunction "D_D") (pintype "passive"))
    )
    (net (code "61") (name "unconnected-(IC1A-G-Pad13)") (class "Default")
      (node (ref "IC1") (pin "13") (pinfunction "G_13") (pintype "input"))
    )
    (net (code "62") (name "unconnected-(IC1A-QH*-Pad9)") (class "Default")
      (node (ref "IC1") (pin "9") (pinfunction "QH*_9") (pintype "tri_state"))
    )
    (net (code "63") (name "unconnected-(IC1A-SCK-Pad11)") (class "Default")
      (node (ref "IC1") (pin "11") (pinfunction "SCK_11") (pintype "input"))
    )
    (net (code "64") (name "unconnected-(IC1A-SCL-Pad10)") (class "Default")
      (node (ref "IC1") (pin "10") (pinfunction "SCL_10") (pintype "input"))
    )
    (net (code "65") (name "unconnected-(IC1A-SER-Pad14)") (class "Default")
      (node (ref "IC1") (pin "14") (pinfunction "SER_14") (pintype "input"))
    )
    (net (code "66") (name "unconnected-(IC2A-G-Pad13)") (class "Default")
      (node (ref "IC2") (pin "13") (pinfunction "G_13") (pintype "input"))
    )
    (net (code "67") (name "unconnected-(IC2A-QH*-Pad9)") (class "Default")
      (node (ref "IC2") (pin "9") (pinfunction "QH*_9") (pintype "tri_state"))
    )
    (net (code "68") (name "unconnected-(IC2A-RCK-Pad12)") (class "Default")
      (node (ref "IC2") (pin "12") (pinfunction "RCK_12") (pintype "input"))
    )
    (net (code "69") (name "unconnected-(IC2A-SCK-Pad11)") (class "Default")
      (node (ref "IC2") (pin "11") (pinfunction "SCK_11") (pintype "input"))
    )
    (net (code "70") (name "unconnected-(IC2A-SCL-Pad10)") (class "Default")
      (node (ref "IC2") (pin "10") (pinfunction "SCL_10") (pintype "input"))
    )
    (net (code "71") (name "unconnected-(IC2A-SER-Pad14)") (class "Default")
      (node (ref "IC2") (pin "14") (pinfunction "SER_14") (pintype "input"))
    )
    (net (code "72") (name "unconnected-(IC4A-CLR-Pad9)") (class "Default")
      (node (ref "IC4") (pin "9") (pinfunction "CLR_9") (pintype "input"))
    )
    (net (code "73") (name "unconnected-(SV1-Pad2)") (class "Default")
      (node (ref "SV1") (pin "2") (pinfunction "2_2") (pintype "passive"))
    )
    (net (code "74") (name "unconnected-(SV1-Pad5)") (class "Default")
      (node (ref "SV1") (pin "5") (pinfunction "5_5") (pintype "passive"))
    )
    (net (code "75") (name "unconnected-(SV1-Pad6)") (class "Default")
      (node (ref "SV1") (pin "6") (pinfunction "6_6") (pintype "passive"))
    )
    (net (code "76") (name "unconnected-(SV2-Pad2)") (class "Default")
      (node (ref "SV2") (pin "2") (pinfunction "2_2") (pintype "passive"))
    )
    (net (code "77") (name "unconnected-(SV2-Pad6)") (class "Default")
      (node (ref "SV2") (pin "6") (pinfunction "6_6") (pintype "passive"))
    )
    (net (code "78") (name "unconnected-(SV3-Pad2)") (class "Default")
      (node (ref "SV3") (pin "2") (pinfunction "2_2") (pintype "passive"))
    )
    (net (code "79") (name "unconnected-(SV3-Pad5)") (class "Default")
      (node (ref "SV3") (pin "5") (pinfunction "5_5") (pintype "passive"))
    )
    (net (code "80") (name "unconnected-(SV3-Pad6)") (class "Default")
      (node (ref "SV3") (pin "6") (pinfunction "6_6") (pintype "passive"))
    )
    (net (code "81") (name "unconnected-(SV4-Pad2)") (class "Default")
      (node (ref "SV4") (pin "2") (pinfunction "2_2") (pintype "passive"))
    )
    (net (code "82") (name "unconnected-(SV4-Pad6)") (class "Default")
      (node (ref "SV4") (pin "6") (pinfunction "6_6") (pintype "passive"))
    )
    (net (code "83") (name "unconnected-(U2-PB0(ICP)-Pad14)") (class "Default")
      (node (ref "U2") (pin "14") (pinfunction "PB0(ICP)_14") (pintype "bidirectional"))
    )
    (net (code "84") (name "unconnected-(U2-PB1(OC1A)-Pad15)") (class "Default")
      (node (ref "U2") (pin "15") (pinfunction "PB1(OC1A)_15") (pintype "bidirectional"))
    )
    (net (code "85") (name "unconnected-(U2-PB2(SS{slash}OC1B)-Pad16)") (class "Default")
      (node (ref "U2") (pin "16") (pinfunction "PB2(SS/OC1B)_16") (pintype "bidirectional"))
    )
    (net (code "86") (name "unconnected-(U2-PB3(MOSI{slash}OC2)-Pad17)") (class "Default")
      (node (ref "U2") (pin "17") (pinfunction "PB3(MOSI/OC2)_17") (pintype "bidirectional"))
    )
    (net (code "87") (name "unconnected-(U2-PB4(MISO)-Pad18)") (class "Default")
      (node (ref "U2") (pin "18") (pinfunction "PB4(MISO)_18") (pintype "bidirectional"))
    )
    (net (code "88") (name "unconnected-(U2-PB5(SCK)-Pad19)") (class "Default")
      (node (ref "U2") (pin "19") (pinfunction "PB5(SCK)_19") (pintype "bidirectional"))
    )
    (net (code "89") (name "unconnected-(U2-PB6(XTAL1{slash}TOSC1)-Pad9)") (class "Default")
      (node (ref "U2") (pin "9") (pinfunction "PB6(XTAL1/TOSC1)_9") (pintype "bidirectional"))
    )
    (net (code "90") (name "unconnected-(U2-PB7(XTAL2{slash}TOSC2)-Pad10)") (class "Default")
      (node (ref "U2") (pin "10") (pinfunction "PB7(XTAL2/TOSC2)_10") (pintype "bidirectional"))
    )
    (net (code "91") (name "unconnected-(U2-PC0(ADC0)-Pad23)") (class "Default")
      (node (ref "U2") (pin "23") (pinfunction "PC0(ADC0)_23") (pintype "bidirectional"))
    )
    (net (code "92") (name "unconnected-(U2-PC1(ADC1)-Pad24)") (class "Default")
      (node (ref "U2") (pin "24") (pinfunction "PC1(ADC1)_24") (pintype "bidirectional"))
    )
    (net (code "93") (name "unconnected-(U2-PC2(ADC2)-Pad25)") (class "Default")
      (node (ref "U2") (pin "25") (pinfunction "PC2(ADC2)_25") (pintype "bidirectional"))
    )
    (net (code "94") (name "unconnected-(U2-PC3(ADC3)-Pad26)") (class "Default")
      (node (ref "U2") (pin "26") (pinfunction "PC3(ADC3)_26") (pintype "bidirectional"))
    )
    (net (code "95") (name "unconnected-(U2-PC4(ADC4{slash}SDA)-Pad27)") (class "Default")
      (node (ref "U2") (pin "27") (pinfunction "PC4(ADC4/SDA)_27") (pintype "bidirectional"))
    )
    (net (code "96") (name "unconnected-(U2-PC5(ADC5{slash}SCL)-Pad28)") (class "Default")
      (node (ref "U2") (pin "28") (pinfunction "PC5(ADC5/SCL)_28") (pintype "bidirectional"))
    )
    (net (code "97") (name "unconnected-(U2-PC6({slash}RESET)-Pad1)") (class "Default")
      (node (ref "U2") (pin "1") (pinfunction "PC6(/RESET)_1") (pintype "bidirectional"))
    )
    (net (code "98") (name "unconnected-(U2-PD1(TXD)-Pad3)") (class "Default")
      (node (ref "U2") (pin "3") (pinfunction "PD1(TXD)_3") (pintype "bidirectional"))
    )
    (net (code "99") (name "unconnected-(U2-PD2(INT0)-Pad4)") (class "Default")
      (node (ref "U2") (pin "4") (pinfunction "PD2(INT0)_4") (pintype "bidirectional"))
    )
    (net (code "100") (name "unconnected-(U2-PD3(INT1)-Pad5)") (class "Default")
      (node (ref "U2") (pin "5") (pinfunction "PD3(INT1)_5") (pintype "bidirectional"))
    )
    (net (code "101") (name "unconnected-(U2-PD4(XCK{slash}T0)-Pad6)") (class "Default")
      (node (ref "U2") (pin "6") (pinfunction "PD4(XCK/T0)_6") (pintype "bidirectional"))
    )
    (net (code "102") (name "unconnected-(U2-PD5(T1)-Pad11)") (class "Default")
      (node (ref "U2") (pin "11") (pinfunction "PD5(T1)_11") (pintype "bidirectional"))
    )
    (net (code "103") (name "unconnected-(U2-PD6(AIN0)-Pad12)") (class "Default")
      (node (ref "U2") (pin "12") (pinfunction "PD6(AIN0)_12") (pintype "bidirectional"))
    )
    (net (code "104") (name "unconnected-(U2-PD7(AIN1)-Pad13)") (class "Default")
      (node (ref "U2") (pin "13") (pinfunction "PD7(AIN1)_13") (pintype "bidirectional"))
    )
  )
)
